# arm_route2.net
KiCad netlist of a schematic drawn in EAGLE
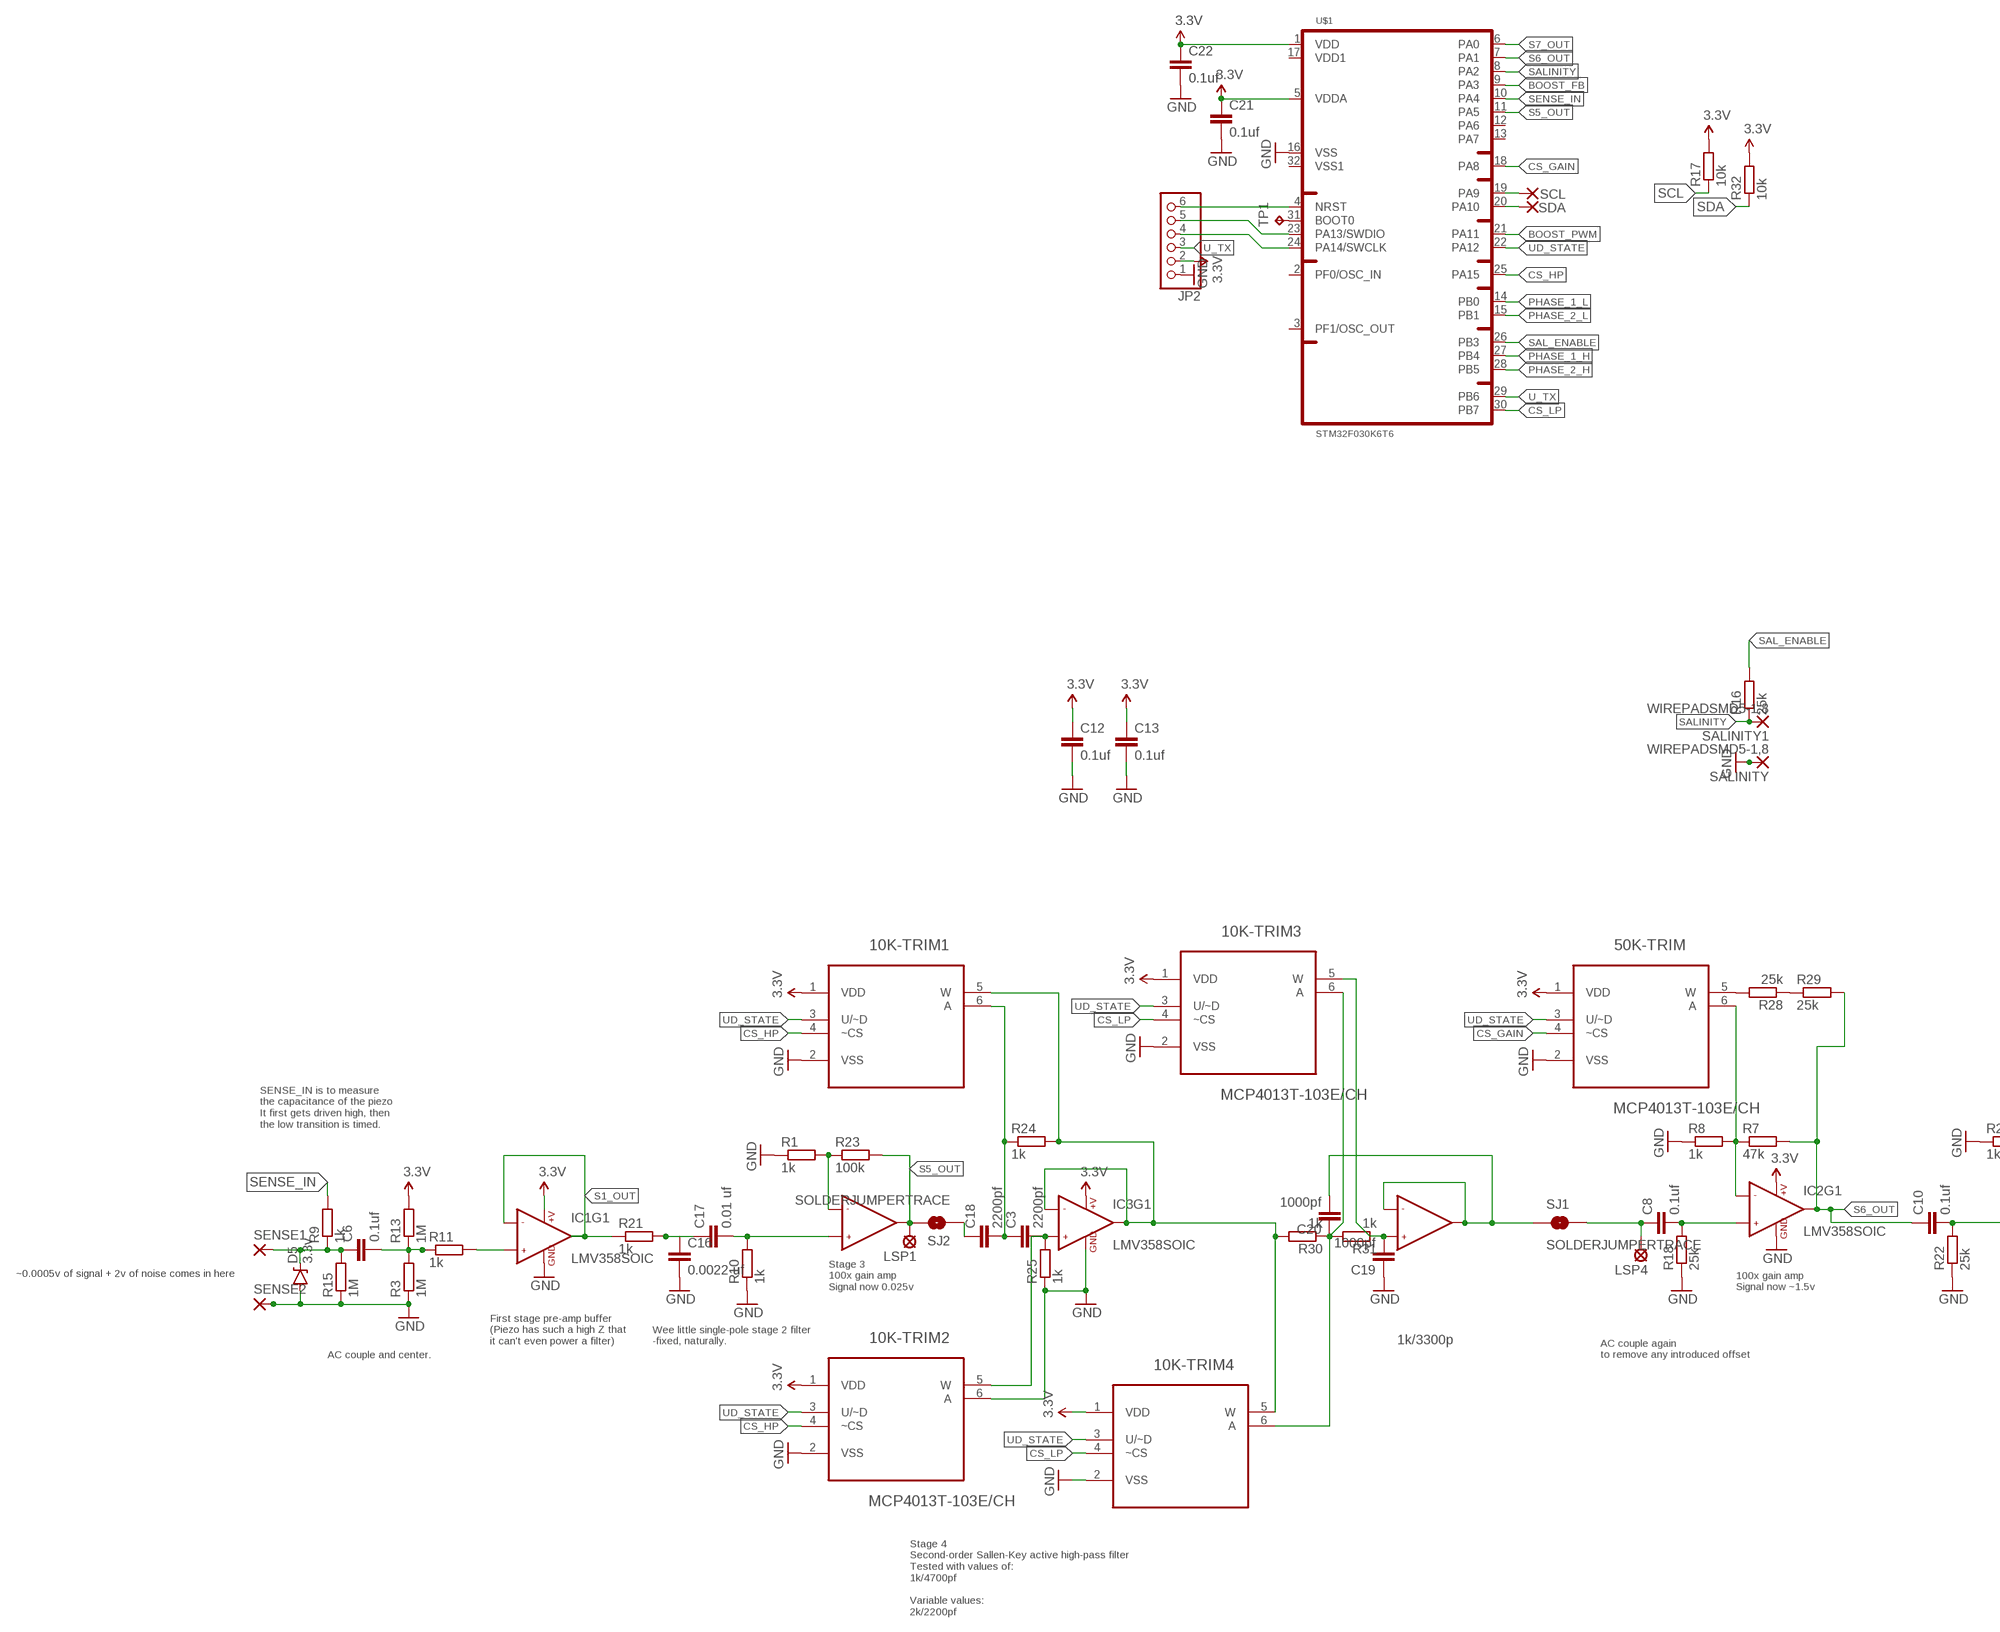
[diagram p0: schematic, sheet 1, part 1 of 2]
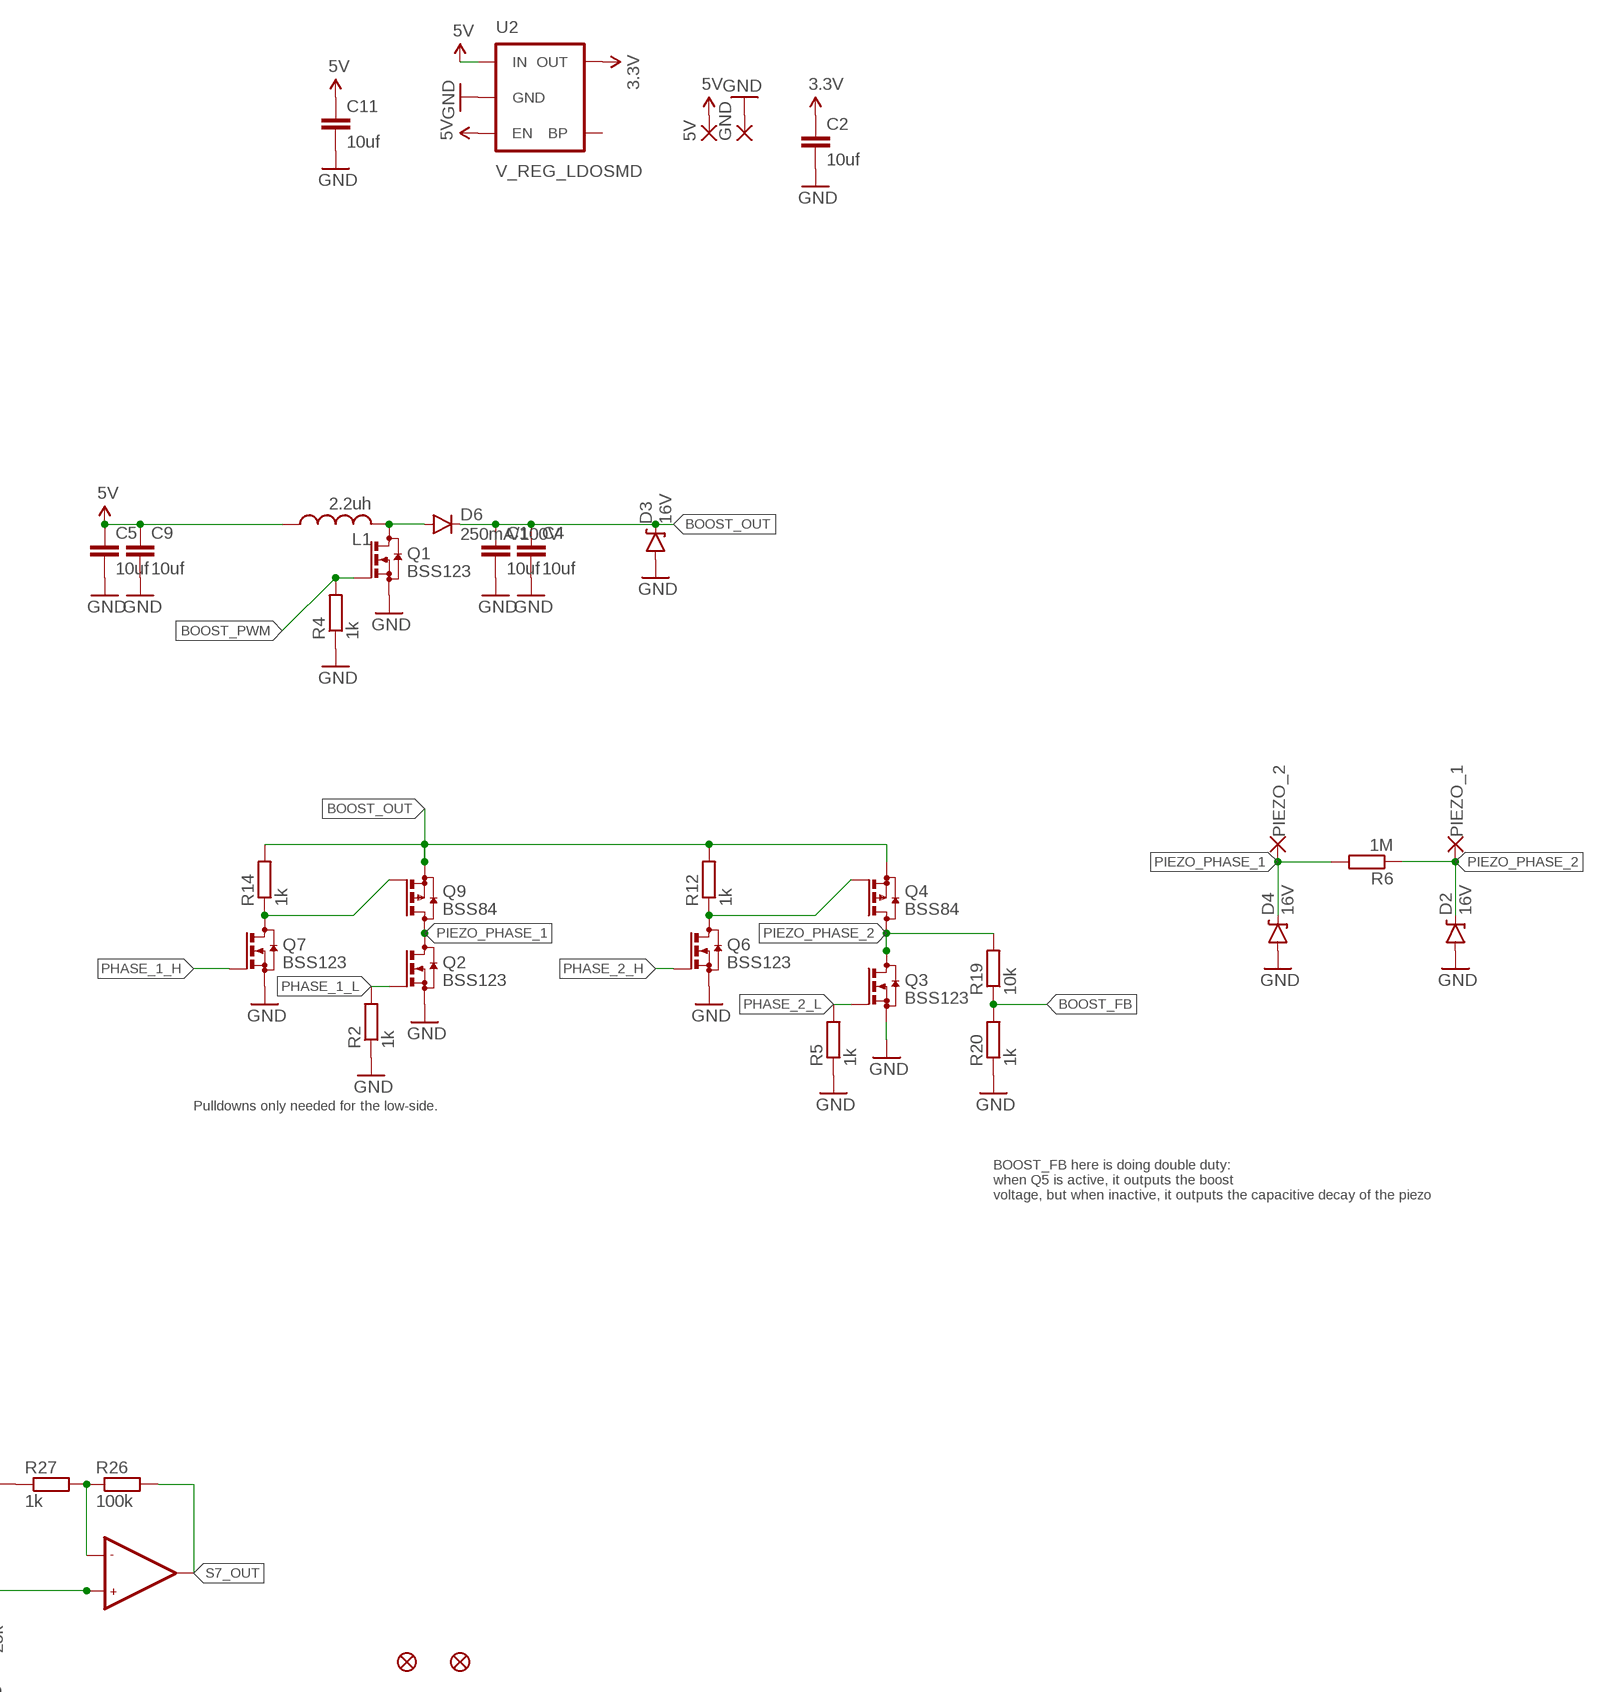
[diagram p1: schematic, sheet 1, part 2 of 2]

(export (version "E")
  (design (tool "Eeschema 10.0.6"))
  (components
    (comp (ref "5V")
      (value "SMD5")
      (footprint "eagle-import:SMD2,54-5,08")
      (libsource (lib "eagle-import") (part "SMD5"))
    )
    (comp (ref "10K-TRIM1")
      (value "MCP4013T-103E/CH")
      (footprint "eagle-import:SOT95P280X145-6N")
      (fields (field (name "DIGI-KEY_PART_NUMBER") "MCP4013T-103E/CHCT-ND") (field (name "MF") "Microchip"))
      (libsource (lib "eagle-import") (part "MCP4013T-103E/CH"))
    )
    (comp (ref "10K-TRIM2")
      (value "MCP4013T-103E/CH")
      (footprint "eagle-import:SOT95P280X145-6N")
      (fields (field (name "DIGI-KEY_PART_NUMBER") "MCP4013T-103E/CHCT-ND") (field (name "MF") "Microchip"))
      (libsource (lib "eagle-import") (part "MCP4013T-103E/CH"))
    )
    (comp (ref "10K-TRIM3")
      (value "MCP4013T-103E/CH")
      (footprint "eagle-import:SOT95P280X145-6N")
      (fields (field (name "DIGI-KEY_PART_NUMBER") "MCP4013T-103E/CHCT-ND") (field (name "MF") "Microchip"))
      (libsource (lib "eagle-import") (part "MCP4013T-103E/CH"))
    )
    (comp (ref "10K-TRIM4")
      (value "MCP4013T-103E/CH")
      (footprint "eagle-import:SOT95P280X145-6N")
      (fields (field (name "DIGI-KEY_PART_NUMBER") "MCP4013T-103E/CHCT-ND") (field (name "MF") "Microchip"))
      (libsource (lib "eagle-import") (part "MCP4013T-103E/CH"))
    )
    (comp (ref "50K-TRIM")
      (value "MCP4013T-103E/CH")
      (footprint "eagle-import:SOT95P280X145-6N")
      (fields (field (name "DIGI-KEY_PART_NUMBER") "MCP4013T-103E/CHCT-ND") (field (name "MF") "Microchip"))
      (libsource (lib "eagle-import") (part "MCP4013T-103E/CH"))
    )
    (comp (ref "C1")
      (value "10uf")
      (footprint "eagle-import:C0805")
      (libsource (lib "eagle-import") (part "C-EUC0805"))
    )
    (comp (ref "C2")
      (value "10uf")
      (footprint "eagle-import:C0603")
      (libsource (lib "eagle-import") (part "C-EUC0603"))
    )
    (comp (ref "C3")
      (value "2200pf")
      (footprint "eagle-import:C0603")
      (libsource (lib "eagle-import") (part "C-EUC0603"))
    )
    (comp (ref "C4")
      (value "10uf")
      (footprint "eagle-import:C0805")
      (libsource (lib "eagle-import") (part "C-EUC0805"))
    )
    (comp (ref "C5")
      (value "10uf")
      (footprint "eagle-import:C0603")
      (libsource (lib "eagle-import") (part "C-EUC0603"))
    )
    (comp (ref "C6")
      (value "0.1uf")
      (footprint "eagle-import:C0603")
      (libsource (lib "eagle-import") (part "C-EUC0603"))
    )
    (comp (ref "C8")
      (value "0.1uf")
      (footprint "eagle-import:C0603")
      (libsource (lib "eagle-import") (part "C-EUC0603"))
    )
    (comp (ref "C9")
      (value "10uf")
      (footprint "eagle-import:C0603")
      (libsource (lib "eagle-import") (part "C-EUC0603"))
    )
    (comp (ref "C10")
      (value "0.1uf")
      (footprint "eagle-import:C0603")
      (libsource (lib "eagle-import") (part "C-EUC0603"))
    )
    (comp (ref "C11")
      (value "10uf")
      (footprint "eagle-import:C0603")
      (libsource (lib "eagle-import") (part "C-EUC0603"))
    )
    (comp (ref "C12")
      (value "0.1uf")
      (footprint "eagle-import:C0603")
      (libsource (lib "eagle-import") (part "C-EUC0603"))
    )
    (comp (ref "C13")
      (value "0.1uf")
      (footprint "eagle-import:C0603")
      (libsource (lib "eagle-import") (part "C-EUC0603"))
    )
    (comp (ref "C16")
      (value "0.0022 uf")
      (footprint "eagle-import:C0603")
      (libsource (lib "eagle-import") (part "C-EUC0603"))
    )
    (comp (ref "C17")
      (value "0.01 uf")
      (footprint "eagle-import:C0603")
      (libsource (lib "eagle-import") (part "C-EUC0603"))
    )
    (comp (ref "C18")
      (value "2200pf")
      (footprint "eagle-import:C0603")
      (libsource (lib "eagle-import") (part "C-EUC0603"))
    )
    (comp (ref "C19")
      (value "1000pf")
      (footprint "eagle-import:C0603")
      (libsource (lib "eagle-import") (part "C-EUC0603"))
    )
    (comp (ref "C20")
      (value "1000pf")
      (footprint "eagle-import:C0603")
      (libsource (lib "eagle-import") (part "C-EUC0603"))
    )
    (comp (ref "C21")
      (value "0.1uf")
      (footprint "eagle-import:C0603")
      (libsource (lib "eagle-import") (part "C-EUC0603"))
    )
    (comp (ref "C22")
      (value "0.1uf")
      (footprint "eagle-import:C0603")
      (libsource (lib "eagle-import") (part "C-EUC0603"))
    )
    (comp (ref "D2")
      (value "16V")
      (footprint "eagle-import:SOD-323")
      (libsource (lib "eagle-import") (part "DIODE-ZENER3.3V"))
    )
    (comp (ref "D3")
      (value "16V")
      (footprint "eagle-import:SOD-323")
      (libsource (lib "eagle-import") (part "DIODE-ZENER3.3V"))
    )
    (comp (ref "D4")
      (value "16V")
      (footprint "eagle-import:SOD-323")
      (libsource (lib "eagle-import") (part "DIODE-ZENER3.3V"))
    )
    (comp (ref "D5")
      (value "3.3v")
      (footprint "eagle-import:SOD-323")
      (libsource (lib "eagle-import") (part "DIODE-ZENER3.3V"))
    )
    (comp (ref "D6")
      (value "250mA/100V")
      (footprint "eagle-import:SOD-323")
      (libsource (lib "eagle-import") (part "DIODEBAS16"))
    )
    (comp (ref "FID1")
      (value "FIDUCIAL1.5X3")
      (footprint "eagle-import:FIDUCIAL-1.5X3")
      (libsource (lib "eagle-import") (part "FIDUCIAL1.5X3"))
    )
    (comp (ref "FID2")
      (value "FIDUCIAL1.5X3")
      (footprint "eagle-import:FIDUCIAL-1.5X3")
      (libsource (lib "eagle-import") (part "FIDUCIAL1.5X3"))
    )
    (comp (ref "GND")
      (value "SMD5")
      (footprint "eagle-import:SMD2,54-5,08")
      (libsource (lib "eagle-import") (part "SMD5"))
    )
    (comp (ref "IC1")
      (value "LMV358SOIC")
      (footprint "eagle-import:SO08")
      (libsource (lib "eagle-import") (part "LMV358SOIC"))
    )
    (comp (ref "IC2")
      (value "LMV358SOIC")
      (footprint "eagle-import:SO08")
      (libsource (lib "eagle-import") (part "LMV358SOIC"))
    )
    (comp (ref "IC3")
      (value "LMV358SOIC")
      (footprint "eagle-import:SO08")
      (libsource (lib "eagle-import") (part "LMV358SOIC"))
    )
    (comp (ref "JP2")
      (value "PINHD-1X6")
      (footprint "eagle-import:1X06")
      (libsource (lib "eagle-import") (part "PINHD-1X6"))
    )
    (comp (ref "L1")
      (value "2.2uh")
      (footprint "eagle-import:L2825P")
      (libsource (lib "eagle-import") (part "L-USL2825P"))
    )
    (comp (ref "LSP1")
      (value "LSP10")
      (footprint "eagle-import:LSP10")
      (libsource (lib "eagle-import") (part "LSP10"))
    )
    (comp (ref "LSP4")
      (value "LSP10")
      (footprint "eagle-import:LSP10")
      (libsource (lib "eagle-import") (part "LSP10"))
    )
    (comp (ref "PIEZO_1")
      (value "SMD5")
      (footprint "eagle-import:SMD2,54-5,08")
      (libsource (lib "eagle-import") (part "SMD5"))
    )
    (comp (ref "PIEZO_2")
      (value "SMD5")
      (footprint "eagle-import:SMD2,54-5,08")
      (libsource (lib "eagle-import") (part "SMD5"))
    )
    (comp (ref "Q1")
      (value "BSS123")
      (footprint "eagle-import:SOT23")
      (libsource (lib "eagle-import") (part "BSS123"))
    )
    (comp (ref "Q2")
      (value "BSS123")
      (footprint "eagle-import:SOT23")
      (libsource (lib "eagle-import") (part "BSS123"))
    )
    (comp (ref "Q3")
      (value "BSS123")
      (footprint "eagle-import:SOT23")
      (libsource (lib "eagle-import") (part "BSS123"))
    )
    (comp (ref "Q4")
      (value "BSS84")
      (footprint "eagle-import:SOT23")
      (libsource (lib "eagle-import") (part "BSS84"))
    )
    (comp (ref "Q6")
      (value "BSS123")
      (footprint "eagle-import:SOT23")
      (libsource (lib "eagle-import") (part "BSS123"))
    )
    (comp (ref "Q7")
      (value "BSS123")
      (footprint "eagle-import:SOT23")
      (libsource (lib "eagle-import") (part "BSS123"))
    )
    (comp (ref "Q9")
      (value "BSS84")
      (footprint "eagle-import:SOT23")
      (libsource (lib "eagle-import") (part "BSS84"))
    )
    (comp (ref "R1")
      (value "1k")
      (footprint "eagle-import:R0603")
      (libsource (lib "eagle-import") (part "R-EU_R0603"))
    )
    (comp (ref "R2")
      (value "1k")
      (footprint "eagle-import:R0603")
      (libsource (lib "eagle-import") (part "R-EU_R0603"))
    )
    (comp (ref "R3")
      (value "1M")
      (footprint "eagle-import:R0603")
      (libsource (lib "eagle-import") (part "R-EU_R0603"))
    )
    (comp (ref "R4")
      (value "1k")
      (footprint "eagle-import:R0603")
      (libsource (lib "eagle-import") (part "R-EU_R0603"))
    )
    (comp (ref "R5")
      (value "1k")
      (footprint "eagle-import:R0603")
      (libsource (lib "eagle-import") (part "R-EU_R0603"))
    )
    (comp (ref "R6")
      (value "1M")
      (footprint "eagle-import:R0603")
      (libsource (lib "eagle-import") (part "R-EU_R0603"))
    )
    (comp (ref "R7")
      (value "47k")
      (footprint "eagle-import:R0603")
      (libsource (lib "eagle-import") (part "R-EU_R0603"))
    )
    (comp (ref "R8")
      (value "1k")
      (footprint "eagle-import:R0603")
      (libsource (lib "eagle-import") (part "R-EU_R0603"))
    )
    (comp (ref "R9")
      (value "1k")
      (footprint "eagle-import:R0603")
      (libsource (lib "eagle-import") (part "R-EU_R0603"))
    )
    (comp (ref "R10")
      (value "1k")
      (footprint "eagle-import:R0603")
      (libsource (lib "eagle-import") (part "R-EU_R0603"))
    )
    (comp (ref "R11")
      (value "1k")
      (footprint "eagle-import:R0603")
      (libsource (lib "eagle-import") (part "R-EU_R0603"))
    )
    (comp (ref "R12")
      (value "1k")
      (footprint "eagle-import:R0603")
      (libsource (lib "eagle-import") (part "R-EU_R0603"))
    )
    (comp (ref "R13")
      (value "1M")
      (footprint "eagle-import:R0603")
      (libsource (lib "eagle-import") (part "R-EU_R0603"))
    )
    (comp (ref "R14")
      (value "1k")
      (footprint "eagle-import:R0603")
      (libsource (lib "eagle-import") (part "R-EU_R0603"))
    )
    (comp (ref "R15")
      (value "1M")
      (footprint "eagle-import:R0603")
      (libsource (lib "eagle-import") (part "R-EU_R0603"))
    )
    (comp (ref "R16")
      (value "25k")
      (footprint "eagle-import:R0603")
      (libsource (lib "eagle-import") (part "R-EU_R0603"))
    )
    (comp (ref "R17")
      (value "10k")
      (footprint "eagle-import:R0603")
      (libsource (lib "eagle-import") (part "R-EU_R0603"))
    )
    (comp (ref "R18")
      (value "25k")
      (footprint "eagle-import:R0603")
      (libsource (lib "eagle-import") (part "R-EU_R0603"))
    )
    (comp (ref "R19")
      (value "10k")
      (footprint "eagle-import:R0603")
      (libsource (lib "eagle-import") (part "R-EU_R0603"))
    )
    (comp (ref "R20")
      (value "1k")
      (footprint "eagle-import:R0603")
      (libsource (lib "eagle-import") (part "R-EU_R0603"))
    )
    (comp (ref "R21")
      (value "1k")
      (footprint "eagle-import:R0603")
      (libsource (lib "eagle-import") (part "R-EU_R0603"))
    )
    (comp (ref "R22")
      (value "25k")
      (footprint "eagle-import:R0603")
      (libsource (lib "eagle-import") (part "R-EU_R0603"))
    )
    (comp (ref "R23")
      (value "100k")
      (footprint "eagle-import:R0603")
      (libsource (lib "eagle-import") (part "R-EU_R0603"))
    )
    (comp (ref "R24")
      (value "1k")
      (footprint "eagle-import:R0603")
      (libsource (lib "eagle-import") (part "R-EU_R0603"))
    )
    (comp (ref "R25")
      (value "1k")
      (footprint "eagle-import:R0603")
      (libsource (lib "eagle-import") (part "R-EU_R0603"))
    )
    (comp (ref "R26")
      (value "100k")
      (footprint "eagle-import:R0603")
      (libsource (lib "eagle-import") (part "R-EU_R0603"))
    )
    (comp (ref "R27")
      (value "1k")
      (footprint "eagle-import:R0603")
      (libsource (lib "eagle-import") (part "R-EU_R0603"))
    )
    (comp (ref "R28")
      (value "25k")
      (footprint "eagle-import:R0603")
      (libsource (lib "eagle-import") (part "R-EU_R0603"))
    )
    (comp (ref "R29")
      (value "25k")
      (footprint "eagle-import:R0603")
      (libsource (lib "eagle-import") (part "R-EU_R0603"))
    )
    (comp (ref "R30")
      (value "1k")
      (footprint "eagle-import:R0603")
      (libsource (lib "eagle-import") (part "R-EU_R0603"))
    )
    (comp (ref "R31")
      (value "1k")
      (footprint "eagle-import:R0603")
      (libsource (lib "eagle-import") (part "R-EU_R0603"))
    )
    (comp (ref "R32")
      (value "10k")
      (footprint "eagle-import:R0603")
      (libsource (lib "eagle-import") (part "R-EU_R0603"))
    )
    (comp (ref "SALINITY")
      (value "WIREPADSMD5-1,8")
      (footprint "eagle-import:5-1,8")
      (libsource (lib "eagle-import") (part "WIREPADSMD5-1,8"))
    )
    (comp (ref "SALINITY1")
      (value "WIREPADSMD5-1,8")
      (footprint "eagle-import:5-1,8")
      (libsource (lib "eagle-import") (part "WIREPADSMD5-1,8"))
    )
    (comp (ref "SCL")
      (value "SMD5")
      (footprint "eagle-import:SMD2,54-5,08")
      (libsource (lib "eagle-import") (part "SMD5"))
    )
    (comp (ref "SDA")
      (value "SMD5")
      (footprint "eagle-import:SMD2,54-5,08")
      (libsource (lib "eagle-import") (part "SMD5"))
    )
    (comp (ref "SENSE1")
      (value "SMD5")
      (footprint "eagle-import:SMD2,54-5,08")
      (libsource (lib "eagle-import") (part "SMD5"))
    )
    (comp (ref "SENSE2")
      (value "SMD5")
      (footprint "eagle-import:SMD2,54-5,08")
      (libsource (lib "eagle-import") (part "SMD5"))
    )
    (comp (ref "SJ1")
      (value "SOLDERJUMPERTRACE")
      (footprint "eagle-import:SJ_2S-TRACE")
      (libsource (lib "eagle-import") (part "SOLDERJUMPERTRACE"))
    )
    (comp (ref "SJ2")
      (value "SOLDERJUMPERTRACE")
      (footprint "eagle-import:SJ_2S-TRACE")
      (libsource (lib "eagle-import") (part "SOLDERJUMPERTRACE"))
    )
    (comp (ref "TP1")
      (value "TPTP12R")
      (footprint "eagle-import:TP12R")
      (libsource (lib "eagle-import") (part "TPTP12R"))
    )
    (comp (ref "U$1")
      (value "STM32F030K6T6")
      (footprint "eagle-import:LQFP-32")
      (libsource (lib "eagle-import") (part "STM32F030K6T6"))
    )
    (comp (ref "U2")
      (value "V_REG_LDOSMD")
      (footprint "eagle-import:SOT23-5")
      (libsource (lib "eagle-import") (part "V_REG_LDOSMD"))
    )
  )
  (nets
    (net (code "1") (name "3.3V") (class "Default")
      (node (ref "10K-TRIM1") (pin "1") (pinfunction "VDD_1") (pintype "power_in"))
      (node (ref "10K-TRIM2") (pin "1") (pinfunction "VDD_1") (pintype "power_in"))
      (node (ref "10K-TRIM3") (pin "1") (pinfunction "VDD_1") (pintype "power_in"))
      (node (ref "10K-TRIM4") (pin "1") (pinfunction "VDD_1") (pintype "power_in"))
      (node (ref "50K-TRIM") (pin "1") (pinfunction "VDD_1") (pintype "power_in"))
      (node (ref "C12") (pin "1") (pinfunction "1_1") (pintype "passive"))
      (node (ref "C13") (pin "1") (pinfunction "1_1") (pintype "passive"))
      (node (ref "C2") (pin "1") (pinfunction "1_1") (pintype "passive"))
      (node (ref "C21") (pin "1") (pinfunction "1_1") (pintype "passive"))
      (node (ref "C22") (pin "1") (pinfunction "1_1") (pintype "passive"))
      (node (ref "IC1") (pin "8") (pinfunction "+V_8") (pintype "power_in"))
      (node (ref "IC2") (pin "8") (pinfunction "+V_8") (pintype "power_in"))
      (node (ref "IC3") (pin "8") (pinfunction "+V_8") (pintype "power_in"))
      (node (ref "JP2") (pin "2") (pinfunction "2_2") (pintype "passive"))
      (node (ref "R13") (pin "2") (pinfunction "2_2") (pintype "passive"))
      (node (ref "R17") (pin "2") (pinfunction "2_2") (pintype "passive"))
      (node (ref "R32") (pin "2") (pinfunction "2_2") (pintype "passive"))
      (node (ref "U$1") (pin "1") (pinfunction "VDD_1") (pintype "bidirectional"))
      (node (ref "U$1") (pin "5") (pinfunction "VDDA_5") (pintype "bidirectional"))
      (node (ref "U2") (pin "5") (pinfunction "OUT_5") (pintype "passive"))
    )
    (net (code "2") (name "5V") (class "Default")
      (node (ref "5V") (pin "1") (pinfunction "P_1") (pintype "passive"))
      (node (ref "C11") (pin "1") (pinfunction "1_1") (pintype "passive"))
      (node (ref "C5") (pin "1") (pinfunction "1_1") (pintype "passive"))
      (node (ref "C9") (pin "1") (pinfunction "1_1") (pintype "passive"))
      (node (ref "L1") (pin "1") (pinfunction "1_1") (pintype "passive"))
      (node (ref "U2") (pin "1") (pinfunction "IN_1") (pintype "input"))
      (node (ref "U2") (pin "3") (pinfunction "EN_3") (pintype "input"))
    )
    (net (code "3") (name "BOOST_FB") (class "Default")
      (node (ref "R19") (pin "1") (pinfunction "1_1") (pintype "passive"))
      (node (ref "R20") (pin "2") (pinfunction "2_2") (pintype "passive"))
      (node (ref "U$1") (pin "9") (pinfunction "PA3_9") (pintype "bidirectional"))
    )
    (net (code "4") (name "BOOST_OUT") (class "Default")
      (node (ref "C1") (pin "1") (pinfunction "1_1") (pintype "passive"))
      (node (ref "C4") (pin "1") (pinfunction "1_1") (pintype "passive"))
      (node (ref "D3") (pin "C") (pinfunction "C_C") (pintype "passive"))
      (node (ref "D6") (pin "C") (pinfunction "C_C") (pintype "passive"))
      (node (ref "Q4") (pin "2") (pinfunction "S_2") (pintype "passive"))
      (node (ref "Q9") (pin "2") (pinfunction "S_2") (pintype "passive"))
      (node (ref "R12") (pin "2") (pinfunction "2_2") (pintype "passive"))
      (node (ref "R14") (pin "2") (pinfunction "2_2") (pintype "passive"))
    )
    (net (code "5") (name "BOOST_PWM") (class "Default")
      (node (ref "Q1") (pin "1") (pinfunction "G_1") (pintype "passive"))
      (node (ref "R4") (pin "2") (pinfunction "2_2") (pintype "passive"))
      (node (ref "U$1") (pin "21") (pinfunction "PA11_21") (pintype "bidirectional"))
    )
    (net (code "6") (name "CS_GAIN") (class "Default")
      (node (ref "50K-TRIM") (pin "4") (pinfunction "~{CS}_4") (pintype "input"))
      (node (ref "U$1") (pin "18") (pinfunction "PA8_18") (pintype "bidirectional"))
    )
    (net (code "7") (name "CS_HP") (class "Default")
      (node (ref "10K-TRIM1") (pin "4") (pinfunction "~{CS}_4") (pintype "input"))
      (node (ref "10K-TRIM2") (pin "4") (pinfunction "~{CS}_4") (pintype "input"))
      (node (ref "U$1") (pin "25") (pinfunction "PA15_25") (pintype "bidirectional"))
    )
    (net (code "8") (name "CS_LP") (class "Default")
      (node (ref "10K-TRIM3") (pin "4") (pinfunction "~{CS}_4") (pintype "input"))
      (node (ref "10K-TRIM4") (pin "4") (pinfunction "~{CS}_4") (pintype "input"))
      (node (ref "U$1") (pin "30") (pinfunction "PB7_30") (pintype "bidirectional"))
    )
    (net (code "9") (name "GND") (class "Default")
      (node (ref "10K-TRIM1") (pin "2") (pinfunction "VSS_2") (pintype "power_in"))
      (node (ref "10K-TRIM2") (pin "2") (pinfunction "VSS_2") (pintype "power_in"))
      (node (ref "10K-TRIM2") (pin "6") (pinfunction "A_6") (pintype "passive"))
      (node (ref "10K-TRIM3") (pin "2") (pinfunction "VSS_2") (pintype "power_in"))
      (node (ref "10K-TRIM4") (pin "2") (pinfunction "VSS_2") (pintype "power_in"))
      (node (ref "50K-TRIM") (pin "2") (pinfunction "VSS_2") (pintype "power_in"))
      (node (ref "C1") (pin "2") (pinfunction "2_2") (pintype "passive"))
      (node (ref "C11") (pin "2") (pinfunction "2_2") (pintype "passive"))
      (node (ref "C12") (pin "2") (pinfunction "2_2") (pintype "passive"))
      (node (ref "C13") (pin "2") (pinfunction "2_2") (pintype "passive"))
      (node (ref "C16") (pin "2") (pinfunction "2_2") (pintype "passive"))
      (node (ref "C19") (pin "1") (pinfunction "1_1") (pintype "passive"))
      (node (ref "C2") (pin "2") (pinfunction "2_2") (pintype "passive"))
      (node (ref "C21") (pin "2") (pinfunction "2_2") (pintype "passive"))
      (node (ref "C22") (pin "2") (pinfunction "2_2") (pintype "passive"))
      (node (ref "C4") (pin "2") (pinfunction "2_2") (pintype "passive"))
      (node (ref "C5") (pin "2") (pinfunction "2_2") (pintype "passive"))
      (node (ref "C9") (pin "2") (pinfunction "2_2") (pintype "passive"))
      (node (ref "D2") (pin "A") (pinfunction "A_A") (pintype "passive"))
      (node (ref "D3") (pin "A") (pinfunction "A_A") (pintype "passive"))
      (node (ref "D4") (pin "A") (pinfunction "A_A") (pintype "passive"))
      (node (ref "D5") (pin "A") (pinfunction "A_A") (pintype "passive"))
      (node (ref "GND") (pin "1") (pinfunction "P_1") (pintype "passive"))
      (node (ref "IC1") (pin "4") (pinfunction "GND_4") (pintype "power_in"))
      (node (ref "IC2") (pin "4") (pinfunction "GND_4") (pintype "power_in"))
      (node (ref "IC3") (pin "4") (pinfunction "GND_4") (pintype "power_in"))
      (node (ref "JP2") (pin "1") (pinfunction "1_1") (pintype "passive"))
      (node (ref "Q1") (pin "2") (pinfunction "S_2") (pintype "passive"))
      (node (ref "Q2") (pin "2") (pinfunction "S_2") (pintype "passive"))
      (node (ref "Q3") (pin "2") (pinfunction "S_2") (pintype "passive"))
      (node (ref "Q6") (pin "2") (pinfunction "S_2") (pintype "passive"))
      (node (ref "Q7") (pin "2") (pinfunction "S_2") (pintype "passive"))
      (node (ref "R1") (pin "1") (pinfunction "1_1") (pintype "passive"))
      (node (ref "R10") (pin "1") (pinfunction "1_1") (pintype "passive"))
      (node (ref "R15") (pin "1") (pinfunction "1_1") (pintype "passive"))
      (node (ref "R18") (pin "1") (pinfunction "1_1") (pintype "passive"))
      (node (ref "R2") (pin "1") (pinfunction "1_1") (pintype "passive"))
      (node (ref "R20") (pin "1") (pinfunction "1_1") (pintype "passive"))
      (node (ref "R22") (pin "1") (pinfunction "1_1") (pintype "passive"))
      (node (ref "R25") (pin "1") (pinfunction "1_1") (pintype "passive"))
      (node (ref "R27") (pin "1") (pinfunction "1_1") (pintype "passive"))
      (node (ref "R3") (pin "1") (pinfunction "1_1") (pintype "passive"))
      (node (ref "R4") (pin "1") (pinfunction "1_1") (pintype "passive"))
      (node (ref "R5") (pin "1") (pinfunction "1_1") (pintype "passive"))
      (node (ref "R8") (pin "1") (pinfunction "1_1") (pintype "passive"))
      (node (ref "SALINITY") (pin "1") (pinfunction "P_1") (pintype "passive"))
      (node (ref "SENSE2") (pin "1") (pinfunction "P_1") (pintype "passive"))
      (node (ref "U$1") (pin "16") (pinfunction "VSS_16") (pintype "bidirectional"))
      (node (ref "U2") (pin "2") (pinfunction "GND_2") (pintype "input"))
    )
    (net (code "10") (name "Net-(10K-TRIM1-A)") (class "Default")
      (node (ref "10K-TRIM1") (pin "6") (pinfunction "A_6") (pintype "passive"))
      (node (ref "C18") (pin "2") (pinfunction "2_2") (pintype "passive"))
      (node (ref "C3") (pin "1") (pinfunction "1_1") (pintype "passive"))
      (node (ref "R24") (pin "1") (pinfunction "1_1") (pintype "passive"))
    )
    (net (code "11") (name "Net-(10K-TRIM1-W)") (class "Default")
      (node (ref "10K-TRIM1") (pin "5") (pinfunction "W_5") (pintype "passive"))
      (node (ref "10K-TRIM4") (pin "5") (pinfunction "W_5") (pintype "passive"))
      (node (ref "IC3") (pin "1") (pinfunction "OUT1_1") (pintype "output"))
      (node (ref "IC3") (pin "2") (pinfunction "-IN1_2") (pintype "input"))
      (node (ref "R24") (pin "2") (pinfunction "2_2") (pintype "passive"))
      (node (ref "R30") (pin "2") (pinfunction "2_2") (pintype "passive"))
    )
    (net (code "12") (name "Net-(10K-TRIM2-W)") (class "Default")
      (node (ref "10K-TRIM2") (pin "5") (pinfunction "W_5") (pintype "passive"))
      (node (ref "C3") (pin "2") (pinfunction "2_2") (pintype "passive"))
      (node (ref "IC3") (pin "3") (pinfunction "+IN1_3") (pintype "input"))
      (node (ref "R25") (pin "2") (pinfunction "2_2") (pintype "passive"))
    )
    (net (code "13") (name "Net-(10K-TRIM3-A)") (class "Default")
      (node (ref "10K-TRIM3") (pin "6") (pinfunction "A_6") (pintype "passive"))
      (node (ref "10K-TRIM4") (pin "6") (pinfunction "A_6") (pintype "passive"))
      (node (ref "C20") (pin "1") (pinfunction "1_1") (pintype "passive"))
      (node (ref "R30") (pin "1") (pinfunction "1_1") (pintype "passive"))
      (node (ref "R31") (pin "2") (pinfunction "2_2") (pintype "passive"))
    )
    (net (code "14") (name "Net-(10K-TRIM3-W)") (class "Default")
      (node (ref "10K-TRIM3") (pin "5") (pinfunction "W_5") (pintype "passive"))
      (node (ref "C19") (pin "2") (pinfunction "2_2") (pintype "passive"))
      (node (ref "IC3") (pin "5") (pinfunction "+IN2_5") (pintype "input"))
      (node (ref "R31") (pin "1") (pinfunction "1_1") (pintype "passive"))
    )
    (net (code "15") (name "Net-(50K-TRIM-A)") (class "Default")
      (node (ref "50K-TRIM") (pin "6") (pinfunction "A_6") (pintype "passive"))
      (node (ref "IC2") (pin "2") (pinfunction "-IN1_2") (pintype "input"))
      (node (ref "R7") (pin "1") (pinfunction "1_1") (pintype "passive"))
      (node (ref "R8") (pin "2") (pinfunction "2_2") (pintype "passive"))
    )
    (net (code "16") (name "Net-(50K-TRIM-W)") (class "Default")
      (node (ref "50K-TRIM") (pin "5") (pinfunction "W_5") (pintype "passive"))
      (node (ref "R28") (pin "2") (pinfunction "2_2") (pintype "passive"))
    )
    (net (code "17") (name "Net-(C6-Pad2)") (class "Default")
      (node (ref "C6") (pin "2") (pinfunction "2_2") (pintype "passive"))
      (node (ref "R11") (pin "1") (pinfunction "1_1") (pintype "passive"))
      (node (ref "R13") (pin "1") (pinfunction "1_1") (pintype "passive"))
      (node (ref "R3") (pin "2") (pinfunction "2_2") (pintype "passive"))
    )
    (net (code "18") (name "Net-(C8-Pad1)") (class "Default")
      (node (ref "C8") (pin "1") (pinfunction "1_1") (pintype "passive"))
      (node (ref "LSP4") (pin "MP") (pinfunction "MP_MP") (pintype "passive"))
      (node (ref "SJ1") (pin "2") (pinfunction "2_2") (pintype "passive"))
    )
    (net (code "19") (name "Net-(C16-Pad1)") (class "Default")
      (node (ref "C16") (pin "1") (pinfunction "1_1") (pintype "passive"))
      (node (ref "C17") (pin "1") (pinfunction "1_1") (pintype "passive"))
      (node (ref "R21") (pin "2") (pinfunction "2_2") (pintype "passive"))
    )
    (net (code "20") (name "Net-(C18-Pad1)") (class "Default")
      (node (ref "C18") (pin "1") (pinfunction "1_1") (pintype "passive"))
      (node (ref "SJ2") (pin "1") (pinfunction "1_1") (pintype "passive"))
    )
    (net (code "21") (name "Net-(IC1A-+IN1)") (class "Default")
      (node (ref "IC1") (pin "3") (pinfunction "+IN1_3") (pintype "input"))
      (node (ref "R11") (pin "2") (pinfunction "2_2") (pintype "passive"))
    )
    (net (code "22") (name "Net-(IC1B-+IN2)") (class "Default")
      (node (ref "C17") (pin "2") (pinfunction "2_2") (pintype "passive"))
      (node (ref "IC1") (pin "5") (pinfunction "+IN2_5") (pintype "input"))
      (node (ref "R10") (pin "2") (pinfunction "2_2") (pintype "passive"))
    )
    (net (code "23") (name "Net-(IC1B--IN2)") (class "Default")
      (node (ref "IC1") (pin "6") (pinfunction "-IN2_6") (pintype "input"))
      (node (ref "R1") (pin "2") (pinfunction "2_2") (pintype "passive"))
      (node (ref "R23") (pin "1") (pinfunction "1_1") (pintype "passive"))
    )
    (net (code "24") (name "Net-(IC2A-+IN1)") (class "Default")
      (node (ref "C8") (pin "2") (pinfunction "2_2") (pintype "passive"))
      (node (ref "IC2") (pin "3") (pinfunction "+IN1_3") (pintype "input"))
      (node (ref "R18") (pin "2") (pinfunction "2_2") (pintype "passive"))
    )
    (net (code "25") (name "Net-(IC2B-+IN2)") (class "Default")
      (node (ref "C10") (pin "2") (pinfunction "2_2") (pintype "passive"))
      (node (ref "IC2") (pin "5") (pinfunction "+IN2_5") (pintype "input"))
      (node (ref "R22") (pin "2") (pinfunction "2_2") (pintype "passive"))
    )
    (net (code "26") (name "Net-(IC2B--IN2)") (class "Default")
      (node (ref "IC2") (pin "6") (pinfunction "-IN2_6") (pintype "input"))
      (node (ref "R26") (pin "1") (pinfunction "1_1") (pintype "passive"))
      (node (ref "R27") (pin "2") (pinfunction "2_2") (pintype "passive"))
    )
    (net (code "27") (name "Net-(IC3B--IN2)") (class "Default")
      (node (ref "C20") (pin "2") (pinfunction "2_2") (pintype "passive"))
      (node (ref "IC3") (pin "6") (pinfunction "-IN2_6") (pintype "input"))
      (node (ref "IC3") (pin "7") (pinfunction "OUT2_7") (pintype "output"))
      (node (ref "SJ1") (pin "1") (pinfunction "1_1") (pintype "passive"))
    )
    (net (code "28") (name "Net-(Q1-D)") (class "Default")
      (node (ref "D6") (pin "A") (pinfunction "A_A") (pintype "passive"))
      (node (ref "L1") (pin "2") (pinfunction "2_2") (pintype "passive"))
      (node (ref "Q1") (pin "3") (pinfunction "D_3") (pintype "passive"))
    )
    (net (code "29") (name "Net-(Q4-G)") (class "Default")
      (node (ref "Q4") (pin "1") (pinfunction "G_1") (pintype "passive"))
      (node (ref "Q6") (pin "3") (pinfunction "D_3") (pintype "passive"))
      (node (ref "R12") (pin "1") (pinfunction "1_1") (pintype "passive"))
    )
    (net (code "30") (name "Net-(Q7-D)") (class "Default")
      (node (ref "Q7") (pin "3") (pinfunction "D_3") (pintype "passive"))
      (node (ref "Q9") (pin "1") (pinfunction "G_1") (pintype "passive"))
      (node (ref "R14") (pin "1") (pinfunction "1_1") (pintype "passive"))
    )
    (net (code "31") (name "Net-(R28-Pad1)") (class "Default")
      (node (ref "R28") (pin "1") (pinfunction "1_1") (pintype "passive"))
      (node (ref "R29") (pin "1") (pinfunction "1_1") (pintype "passive"))
    )
    (net (code "32") (name "Net-(SENSE1-P)") (class "Default")
      (node (ref "C6") (pin "1") (pinfunction "1_1") (pintype "passive"))
      (node (ref "D5") (pin "C") (pinfunction "C_C") (pintype "passive"))
      (node (ref "R15") (pin "2") (pinfunction "2_2") (pintype "passive"))
      (node (ref "R9") (pin "1") (pinfunction "1_1") (pintype "passive"))
      (node (ref "SENSE1") (pin "1") (pinfunction "P_1") (pintype "passive"))
    )
    (net (code "33") (name "Net-(U$1-BOOT0)") (class "Default")
      (node (ref "TP1") (pin "TP") (pinfunction "TP_TP") (pintype "input"))
      (node (ref "U$1") (pin "31") (pinfunction "BOOT0_31") (pintype "bidirectional"))
    )
    (net (code "34") (name "Net-(U$1-NRST)") (class "Default")
      (node (ref "JP2") (pin "6") (pinfunction "6_6") (pintype "passive"))
      (node (ref "U$1") (pin "4") (pinfunction "NRST_4") (pintype "bidirectional"))
    )
    (net (code "35") (name "Net-(U$1-PA13{slash}SWDIO)") (class "Default")
      (node (ref "JP2") (pin "5") (pinfunction "5_5") (pintype "passive"))
      (node (ref "U$1") (pin "23") (pinfunction "PA13/SWDIO_23") (pintype "bidirectional"))
    )
    (net (code "36") (name "Net-(U$1-PA14{slash}SWCLK)") (class "Default")
      (node (ref "JP2") (pin "4") (pinfunction "4_4") (pintype "passive"))
      (node (ref "U$1") (pin "24") (pinfunction "PA14/SWCLK_24") (pintype "bidirectional"))
    )
    (net (code "37") (name "PHASE_1_H") (class "Default")
      (node (ref "Q7") (pin "1") (pinfunction "G_1") (pintype "passive"))
      (node (ref "U$1") (pin "27") (pinfunction "PB4_27") (pintype "bidirectional"))
    )
    (net (code "38") (name "PHASE_1_L") (class "Default")
      (node (ref "Q2") (pin "1") (pinfunction "G_1") (pintype "passive"))
      (node (ref "R2") (pin "2") (pinfunction "2_2") (pintype "passive"))
      (node (ref "U$1") (pin "14") (pinfunction "PB0_14") (pintype "bidirectional"))
    )
    (net (code "39") (name "PHASE_2_H") (class "Default")
      (node (ref "Q6") (pin "1") (pinfunction "G_1") (pintype "passive"))
      (node (ref "U$1") (pin "28") (pinfunction "PB5_28") (pintype "bidirectional"))
    )
    (net (code "40") (name "PHASE_2_L") (class "Default")
      (node (ref "Q3") (pin "1") (pinfunction "G_1") (pintype "passive"))
      (node (ref "R5") (pin "2") (pinfunction "2_2") (pintype "passive"))
      (node (ref "U$1") (pin "15") (pinfunction "PB1_15") (pintype "bidirectional"))
    )
    (net (code "41") (name "PIEZO_PHASE_1") (class "Default")
      (node (ref "D4") (pin "C") (pinfunction "C_C") (pintype "passive"))
      (node (ref "PIEZO_2") (pin "1") (pinfunction "P_1") (pintype "passive"))
      (node (ref "Q2") (pin "3") (pinfunction "D_3") (pintype "passive"))
      (node (ref "Q9") (pin "3") (pinfunction "D_3") (pintype "passive"))
      (node (ref "R6") (pin "2") (pinfunction "2_2") (pintype "passive"))
    )
    (net (code "42") (name "PIEZO_PHASE_2") (class "Default")
      (node (ref "D2") (pin "C") (pinfunction "C_C") (pintype "passive"))
      (node (ref "PIEZO_1") (pin "1") (pinfunction "P_1") (pintype "passive"))
      (node (ref "Q3") (pin "3") (pinfunction "D_3") (pintype "passive"))
      (node (ref "Q4") (pin "3") (pinfunction "D_3") (pintype "passive"))
      (node (ref "R19") (pin "2") (pinfunction "2_2") (pintype "passive"))
      (node (ref "R6") (pin "1") (pinfunction "1_1") (pintype "passive"))
    )
    (net (code "43") (name "S1_OUT") (class "Default")
      (node (ref "IC1") (pin "1") (pinfunction "OUT1_1") (pintype "output"))
      (node (ref "IC1") (pin "2") (pinfunction "-IN1_2") (pintype "input"))
      (node (ref "R21") (pin "1") (pinfunction "1_1") (pintype "passive"))
    )
    (net (code "44") (name "S5_OUT") (class "Default")
      (node (ref "IC1") (pin "7") (pinfunction "OUT2_7") (pintype "output"))
      (node (ref "LSP1") (pin "MP") (pinfunction "MP_MP") (pintype "passive"))
      (node (ref "R23") (pin "2") (pinfunction "2_2") (pintype "passive"))
      (node (ref "SJ2") (pin "2") (pinfunction "2_2") (pintype "passive"))
      (node (ref "U$1") (pin "11") (pinfunction "PA5_11") (pintype "bidirectional"))
    )
    (net (code "45") (name "S6_OUT") (class "Default")
      (node (ref "C10") (pin "1") (pinfunction "1_1") (pintype "passive"))
      (node (ref "IC2") (pin "1") (pinfunction "OUT1_1") (pintype "output"))
      (node (ref "R29") (pin "2") (pinfunction "2_2") (pintype "passive"))
      (node (ref "R7") (pin "2") (pinfunction "2_2") (pintype "passive"))
      (node (ref "U$1") (pin "7") (pinfunction "PA1_7") (pintype "bidirectional"))
    )
    (net (code "46") (name "S7_OUT") (class "Default")
      (node (ref "IC2") (pin "7") (pinfunction "OUT2_7") (pintype "output"))
      (node (ref "R26") (pin "2") (pinfunction "2_2") (pintype "passive"))
      (node (ref "U$1") (pin "6") (pinfunction "PA0_6") (pintype "bidirectional"))
    )
    (net (code "47") (name "SALINITY") (class "Default")
      (node (ref "R16") (pin "1") (pinfunction "1_1") (pintype "passive"))
      (node (ref "SALINITY1") (pin "1") (pinfunction "P_1") (pintype "passive"))
      (node (ref "U$1") (pin "8") (pinfunction "PA2_8") (pintype "bidirectional"))
    )
    (net (code "48") (name "SAL_ENABLE") (class "Default")
      (node (ref "R16") (pin "2") (pinfunction "2_2") (pintype "passive"))
      (node (ref "U$1") (pin "26") (pinfunction "PB3_26") (pintype "bidirectional"))
    )
    (net (code "49") (name "SCL") (class "Default")
      (node (ref "R17") (pin "1") (pinfunction "1_1") (pintype "passive"))
      (node (ref "SCL") (pin "1") (pinfunction "P_1") (pintype "passive"))
      (node (ref "U$1") (pin "19") (pinfunction "PA9_19") (pintype "bidirectional"))
    )
    (net (code "50") (name "SDA") (class "Default")
      (node (ref "R32") (pin "1") (pinfunction "1_1") (pintype "passive"))
      (node (ref "SDA") (pin "1") (pinfunction "P_1") (pintype "passive"))
      (node (ref "U$1") (pin "20") (pinfunction "PA10_20") (pintype "bidirectional"))
    )
    (net (code "51") (name "SENSE_IN") (class "Default")
      (node (ref "R9") (pin "2") (pinfunction "2_2") (pintype "passive"))
      (node (ref "U$1") (pin "10") (pinfunction "PA4_10") (pintype "bidirectional"))
    )
    (net (code "52") (name "UD_STATE") (class "Default")
      (node (ref "10K-TRIM1") (pin "3") (pinfunction "U/~{D}_3") (pintype "input"))
      (node (ref "10K-TRIM2") (pin "3") (pinfunction "U/~{D}_3") (pintype "input"))
      (node (ref "10K-TRIM3") (pin "3") (pinfunction "U/~{D}_3") (pintype "input"))
      (node (ref "10K-TRIM4") (pin "3") (pinfunction "U/~{D}_3") (pintype "input"))
      (node (ref "50K-TRIM") (pin "3") (pinfunction "U/~{D}_3") (pintype "input"))
      (node (ref "U$1") (pin "22") (pinfunction "PA12_22") (pintype "bidirectional"))
    )
    (net (code "53") (name "U_TX") (class "Default")
      (node (ref "JP2") (pin "3") (pinfunction "3_3") (pintype "passive"))
      (node (ref "U$1") (pin "29") (pinfunction "PB6_29") (pintype "bidirectional"))
    )
    (net (code "54") (name "unconnected-(U$1-PA6-Pad12)") (class "Default")
      (node (ref "U$1") (pin "12") (pinfunction "PA6_12") (pintype "bidirectional"))
    )
    (net (code "55") (name "unconnected-(U$1-PA7-Pad13)") (class "Default")
      (node (ref "U$1") (pin "13") (pinfunction "PA7_13") (pintype "bidirectional"))
    )
    (net (code "56") (name "unconnected-(U$1-PF0{slash}OSC_IN-Pad2)") (class "Default")
      (node (ref "U$1") (pin "2") (pinfunction "PF0/OSC_IN_2") (pintype "bidirectional"))
    )
    (net (code "57") (name "unconnected-(U$1-PF1{slash}OSC_OUT-Pad3)") (class "Default")
      (node (ref "U$1") (pin "3") (pinfunction "PF1/OSC_OUT_3") (pintype "bidirectional"))
    )
    (net (code "58") (name "unconnected-(U$1-VDD1-Pad17)") (class "Default")
      (node (ref "U$1") (pin "17") (pinfunction "VDD1_17") (pintype "bidirectional"))
    )
    (net (code "59") (name "unconnected-(U$1-VSS1-Pad32)") (class "Default")
      (node (ref "U$1") (pin "32") (pinfunction "VSS1_32") (pintype "bidirectional"))
    )
    (net (code "60") (name "unconnected-(U2-BP-Pad4)") (class "Default")
      (node (ref "U2") (pin "4") (pinfunction "BP_4") (pintype "input"))
    )
  )
)
